# SCH_Altimeter-Attiny_2021-11-18.net
KiCad netlist of a schematic drawn in EasyEDA
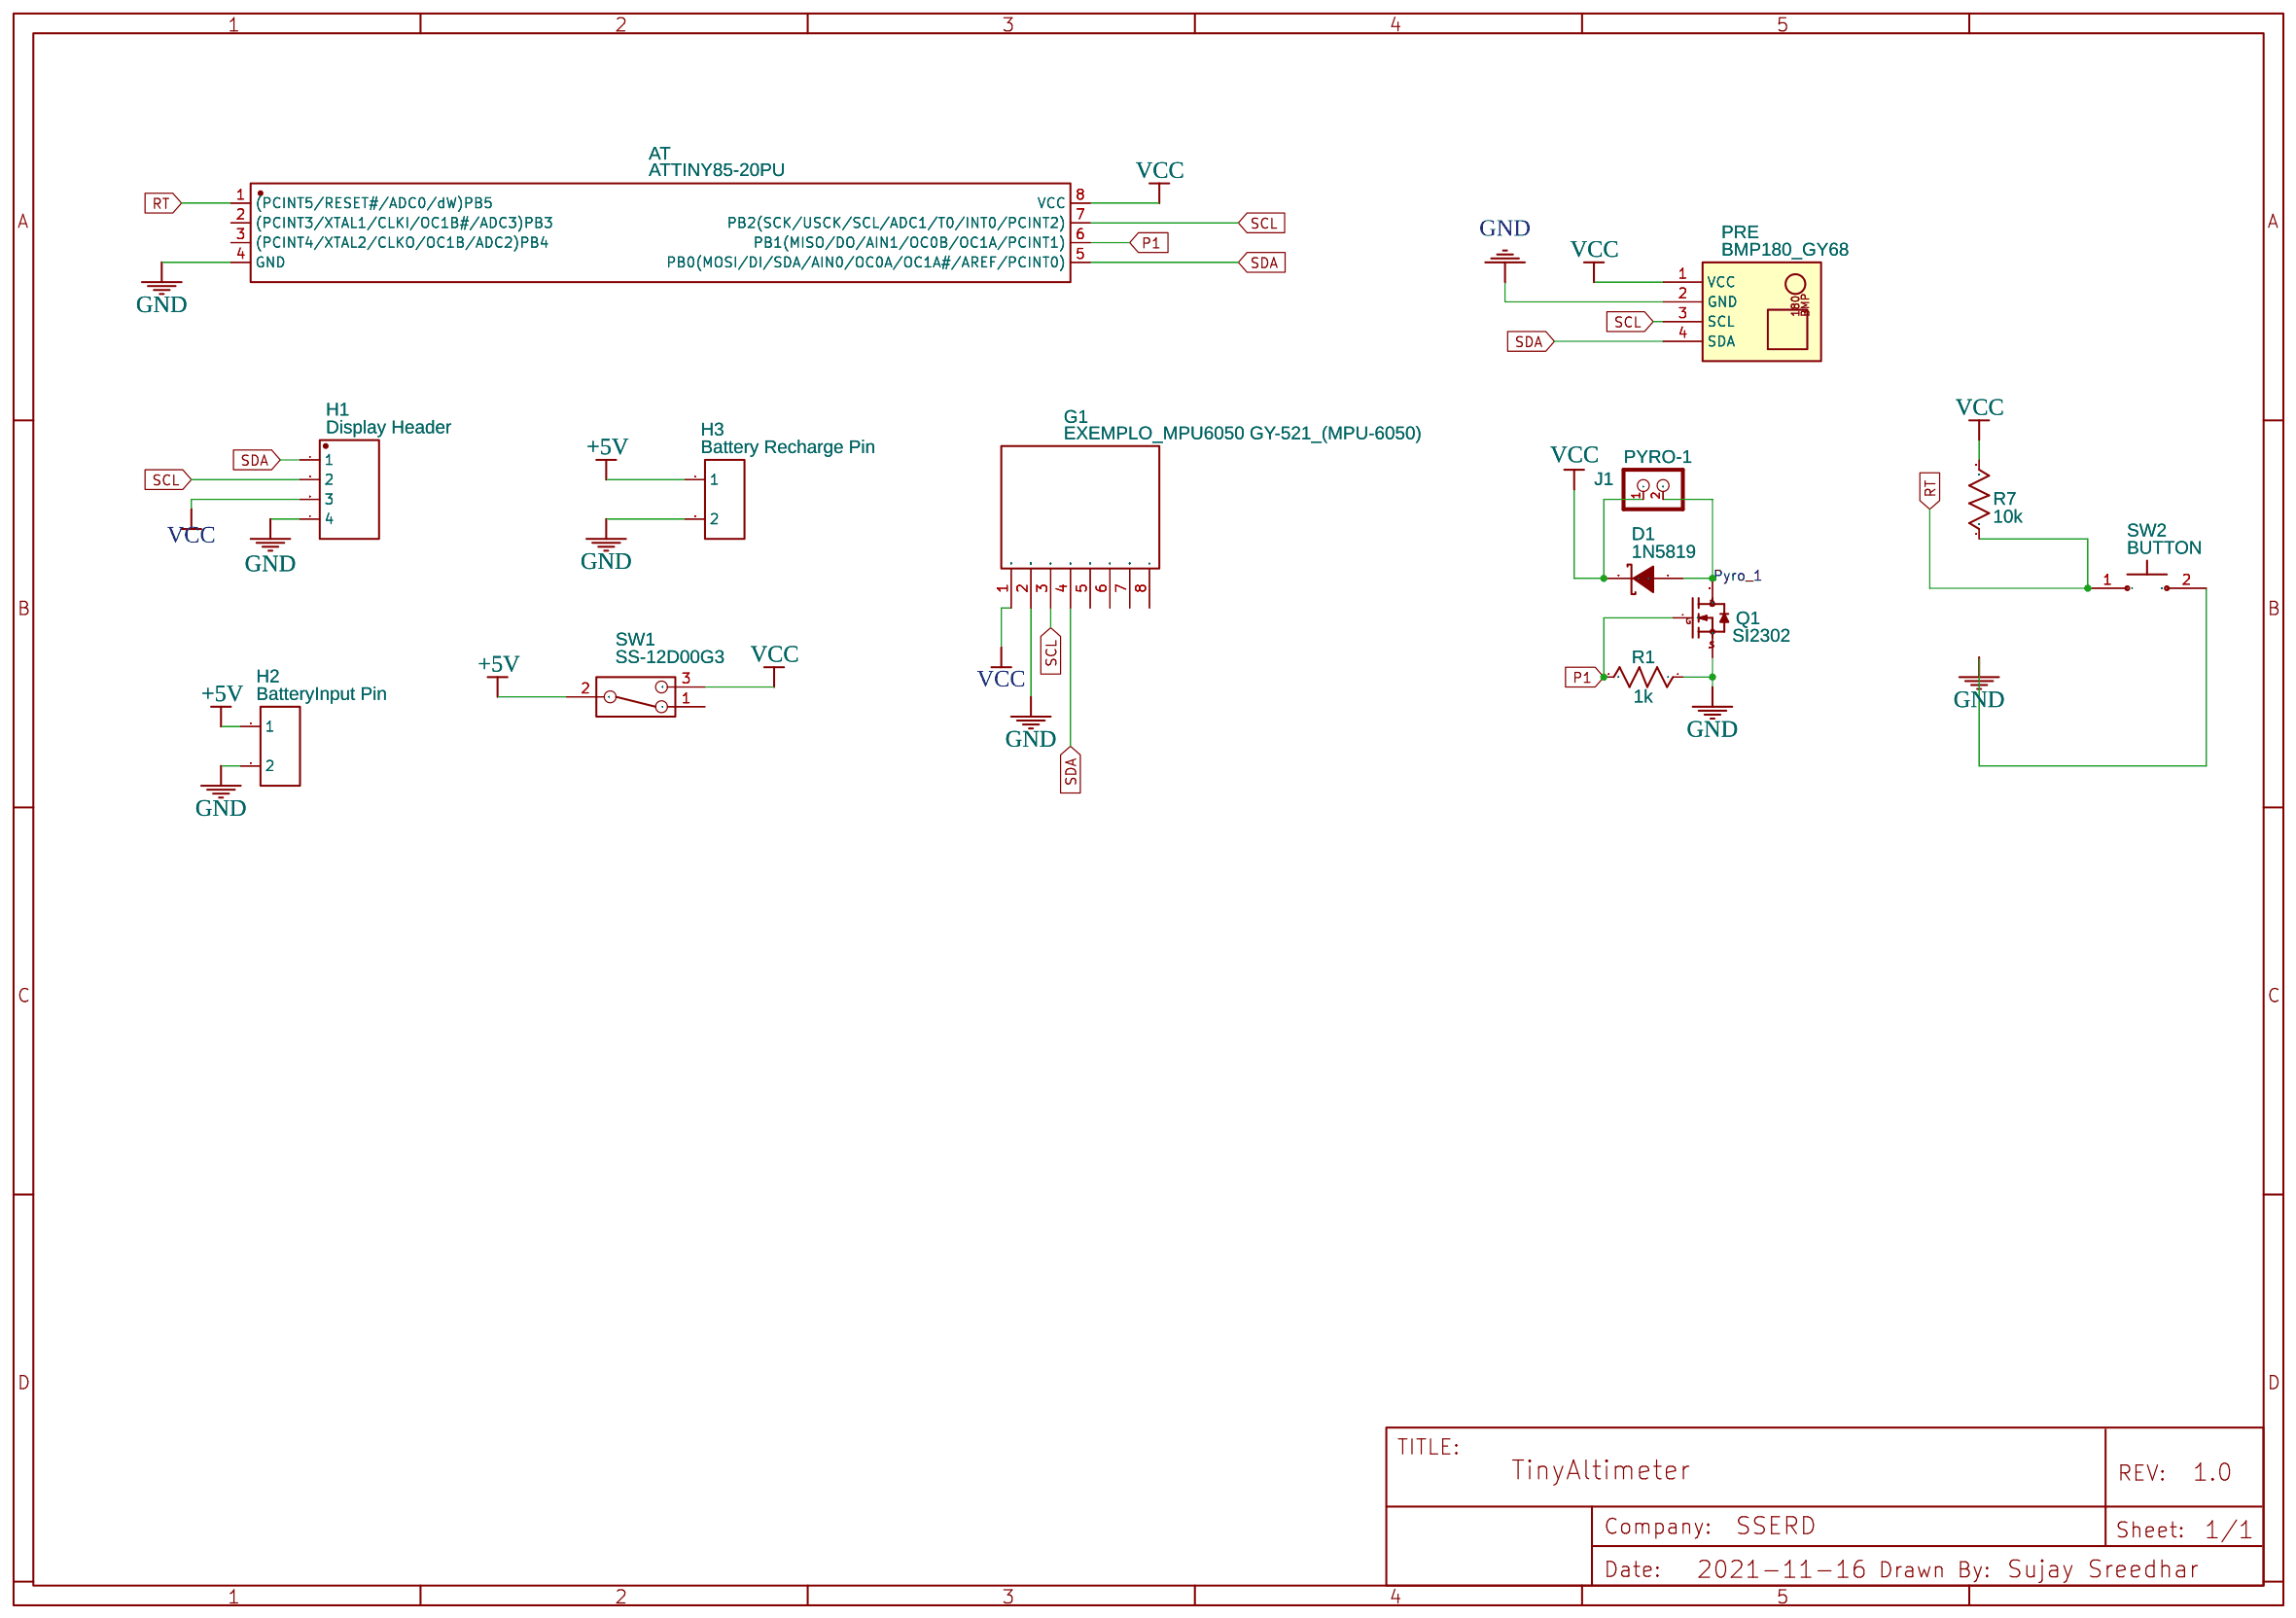
[diagram p0: schematic sheet]

(export (version "E")
  (design (tool "Eeschema 10.0.6"))
  (components
    (comp (ref "AT")
      (value "ATTINY85-20PU")
      (fields (field (name "BOM_Supplier Part") "C965497"))
      (libsource (lib "") (part "ATTINY85-20PU"))
    )
    (comp (ref "D1")
      (value "1N5819")
      (fields (field (name "BOM_Supplier Part") "C110032"))
      (libsource (lib "") (part "1N5819"))
    )
    (comp (ref "G1")
      (value "EXEMPLO_MPU6050 GY-521_(MPU-6050)")
      (fields (field (name "BOM_Manufacturer Part") "GY-521"))
      (libsource (lib "") (part "EXEMPLO_MPU6050 GY-521_(MPU-6050)"))
    )
    (comp (ref "H1")
      (value "Display Header")
      (fields
        (field (name "BOM_Manufacturer Part") "210S-1*4P L=11.6MMGold-plated black")
        (field (name "BOM_Supplier Part") "C124378")
      )
      (libsource (lib "") (part "Header-Male-2.54_1x4"))
    )
    (comp (ref "H2")
      (value "BatteryInput Pin")
      (fields (field (name "BOM_Manufacturer Part") "826629-2") (field (name "BOM_Supplier Part") "C86471"))
      (libsource (lib "") (part "Header-Male-2.54_1x2"))
    )
    (comp (ref "H3")
      (value "Battery Recharge Pin")
      (fields (field (name "BOM_Manufacturer Part") "826629-2") (field (name "BOM_Supplier Part") "C86471"))
      (libsource (lib "") (part "Header-Male-2.54_1x2"))
    )
    (comp (ref "J1") (value "PYRO-1") (libsource (lib "") (part "CON_TERMINAL_BLOCK_02")))
    (comp (ref "PRE") (value "BMP180_GY68") (libsource (lib "") (part "BMP180_GY68")))
    (comp (ref "Q1")
      (value "SI2302")
      (fields (field (name "BOM_Supplier Part") "C181087"))
      (libsource (lib "") (part "SI2302"))
    )
    (comp (ref "R1") (value "1k") (libsource (lib "") (part "R_AXIAL-0.4_US")))
    (comp (ref "R7") (value "10k") (libsource (lib "") (part "R_AXIAL-0.4_US_1")))
    (comp (ref "SW1") (value "SS-12D00G3") (libsource (lib "") (part "SS-12D00G3")))
    (comp (ref "SW2") (value "BUTTON") (libsource (lib "") (part "BUTTON")))
  )
  (nets
    (net (code "1") (name "+5V") (class "Default")
      (node (ref "H2") (pin "1") (pinfunction "1_1") (pintype "unspecified"))
      (node (ref "H3") (pin "1") (pinfunction "1_1") (pintype "unspecified"))
      (node (ref "SW1") (pin "2") (pinfunction "2_2") (pintype "unspecified"))
    )
    (net (code "2") (name "/Pyro_1") (class "Default")
      (node (ref "D1") (pin "1") (pinfunction "A_1") (pintype "unspecified"))
      (node (ref "J1") (pin "2") (pinfunction "2_2") (pintype "unspecified"))
      (node (ref "Q1") (pin "3") (pinfunction "D_3") (pintype "unspecified"))
    )
    (net (code "3") (name "GND") (class "Default")
      (node (ref "AT") (pin "4") (pinfunction "GND_4") (pintype "unspecified"))
      (node (ref "G1") (pin "2") (pinfunction "GND_2") (pintype "unspecified"))
      (node (ref "H1") (pin "4") (pinfunction "4_4") (pintype "unspecified"))
      (node (ref "H2") (pin "2") (pinfunction "2_2") (pintype "unspecified"))
      (node (ref "H3") (pin "2") (pinfunction "2_2") (pintype "unspecified"))
      (node (ref "PRE") (pin "2") (pinfunction "GND_2") (pintype "unspecified"))
      (node (ref "Q1") (pin "2") (pinfunction "S_2") (pintype "unspecified"))
      (node (ref "R1") (pin "1") (pinfunction "1_1") (pintype "unspecified"))
      (node (ref "SW2") (pin "2") (pinfunction "2_2") (pintype "unspecified"))
    )
    (net (code "4") (name "P1") (class "Default")
      (node (ref "AT") (pin "6") (pinfunction "PB1(MISO/DO/AIN1/OC0B/OC1A/PCINT1)_6") (pintype "unspecified"))
      (node (ref "Q1") (pin "1") (pinfunction "G_1") (pintype "unspecified"))
      (node (ref "R1") (pin "2") (pinfunction "2_2") (pintype "unspecified"))
    )
    (net (code "5") (name "RT") (class "Default")
      (node (ref "AT") (pin "1") (pinfunction "(PCINT5/RESET#/ADC0/dW)PB5_1") (pintype "unspecified"))
      (node (ref "R7") (pin "1") (pinfunction "1_1") (pintype "unspecified"))
      (node (ref "SW2") (pin "1") (pinfunction "1_1") (pintype "unspecified"))
    )
    (net (code "6") (name "SCL") (class "Default")
      (node (ref "AT") (pin "7") (pinfunction "PB2(SCK/USCK/SCL/ADC1/T0/INT0/PCINT2)_7") (pintype "unspecified"))
      (node (ref "G1") (pin "3") (pinfunction "SCL_3") (pintype "unspecified"))
      (node (ref "H1") (pin "2") (pinfunction "2_2") (pintype "unspecified"))
      (node (ref "PRE") (pin "3") (pinfunction "SCL_3") (pintype "unspecified"))
    )
    (net (code "7") (name "SDA") (class "Default")
      (node (ref "AT") (pin "5") (pinfunction "PB0(MOSI/DI/SDA/AIN0/OC0A/OC1A#/AREF/PCINT0)_5") (pintype "unspecified"))
      (node (ref "G1") (pin "4") (pinfunction "SDA_4") (pintype "unspecified"))
      (node (ref "H1") (pin "1") (pinfunction "1_1") (pintype "unspecified"))
      (node (ref "PRE") (pin "4") (pinfunction "SDA_4") (pintype "unspecified"))
    )
    (net (code "8") (name "VCC") (class "Default")
      (node (ref "AT") (pin "8") (pinfunction "VCC_8") (pintype "unspecified"))
      (node (ref "D1") (pin "2") (pinfunction "K_2") (pintype "unspecified"))
      (node (ref "G1") (pin "1") (pinfunction "VCC_1") (pintype "unspecified"))
      (node (ref "H1") (pin "3") (pinfunction "3_3") (pintype "unspecified"))
      (node (ref "J1") (pin "1") (pinfunction "1_1") (pintype "unspecified"))
      (node (ref "PRE") (pin "1") (pinfunction "VCC_1") (pintype "unspecified"))
      (node (ref "R7") (pin "2") (pinfunction "2_2") (pintype "unspecified"))
      (node (ref "SW1") (pin "3") (pinfunction "3_3") (pintype "unspecified"))
    )
    (net (code "9") (name "unconnected-(AT-(PCINT3{slash}XTAL1{slash}CLKI{slash}OC1B#{slash}ADC3)PB3-Pad2)") (class "Default")
      (node (ref "AT") (pin "2") (pinfunction "(PCINT3/XTAL1/CLKI/OC1B#/ADC3)PB3_2") (pintype "unspecified"))
    )
    (net (code "10") (name "unconnected-(AT-(PCINT4{slash}XTAL2{slash}CLKO{slash}OC1B{slash}ADC2)PB4-Pad3)") (class "Default")
      (node (ref "AT") (pin "3") (pinfunction "(PCINT4/XTAL2/CLKO/OC1B/ADC2)PB4_3") (pintype "unspecified"))
    )
    (net (code "11") (name "unconnected-(G1-AD0-Pad7)") (class "Default")
      (node (ref "G1") (pin "7") (pinfunction "AD0_7") (pintype "unspecified"))
    )
    (net (code "12") (name "unconnected-(G1-INT-Pad8)") (class "Default")
      (node (ref "G1") (pin "8") (pinfunction "INT_8") (pintype "unspecified"))
    )
    (net (code "13") (name "unconnected-(G1-XCL-Pad6)") (class "Default")
      (node (ref "G1") (pin "6") (pinfunction "XCL_6") (pintype "unspecified"))
    )
    (net (code "14") (name "unconnected-(G1-XDA-Pad5)") (class "Default")
      (node (ref "G1") (pin "5") (pinfunction "XDA_5") (pintype "unspecified"))
    )
    (net (code "15") (name "unconnected-(SW1-Pad1)") (class "Default")
      (node (ref "SW1") (pin "1") (pinfunction "1_1") (pintype "unspecified"))
    )
  )
)
